# slot_imu.net
KiCad netlist of a schematic drawn in EAGLE
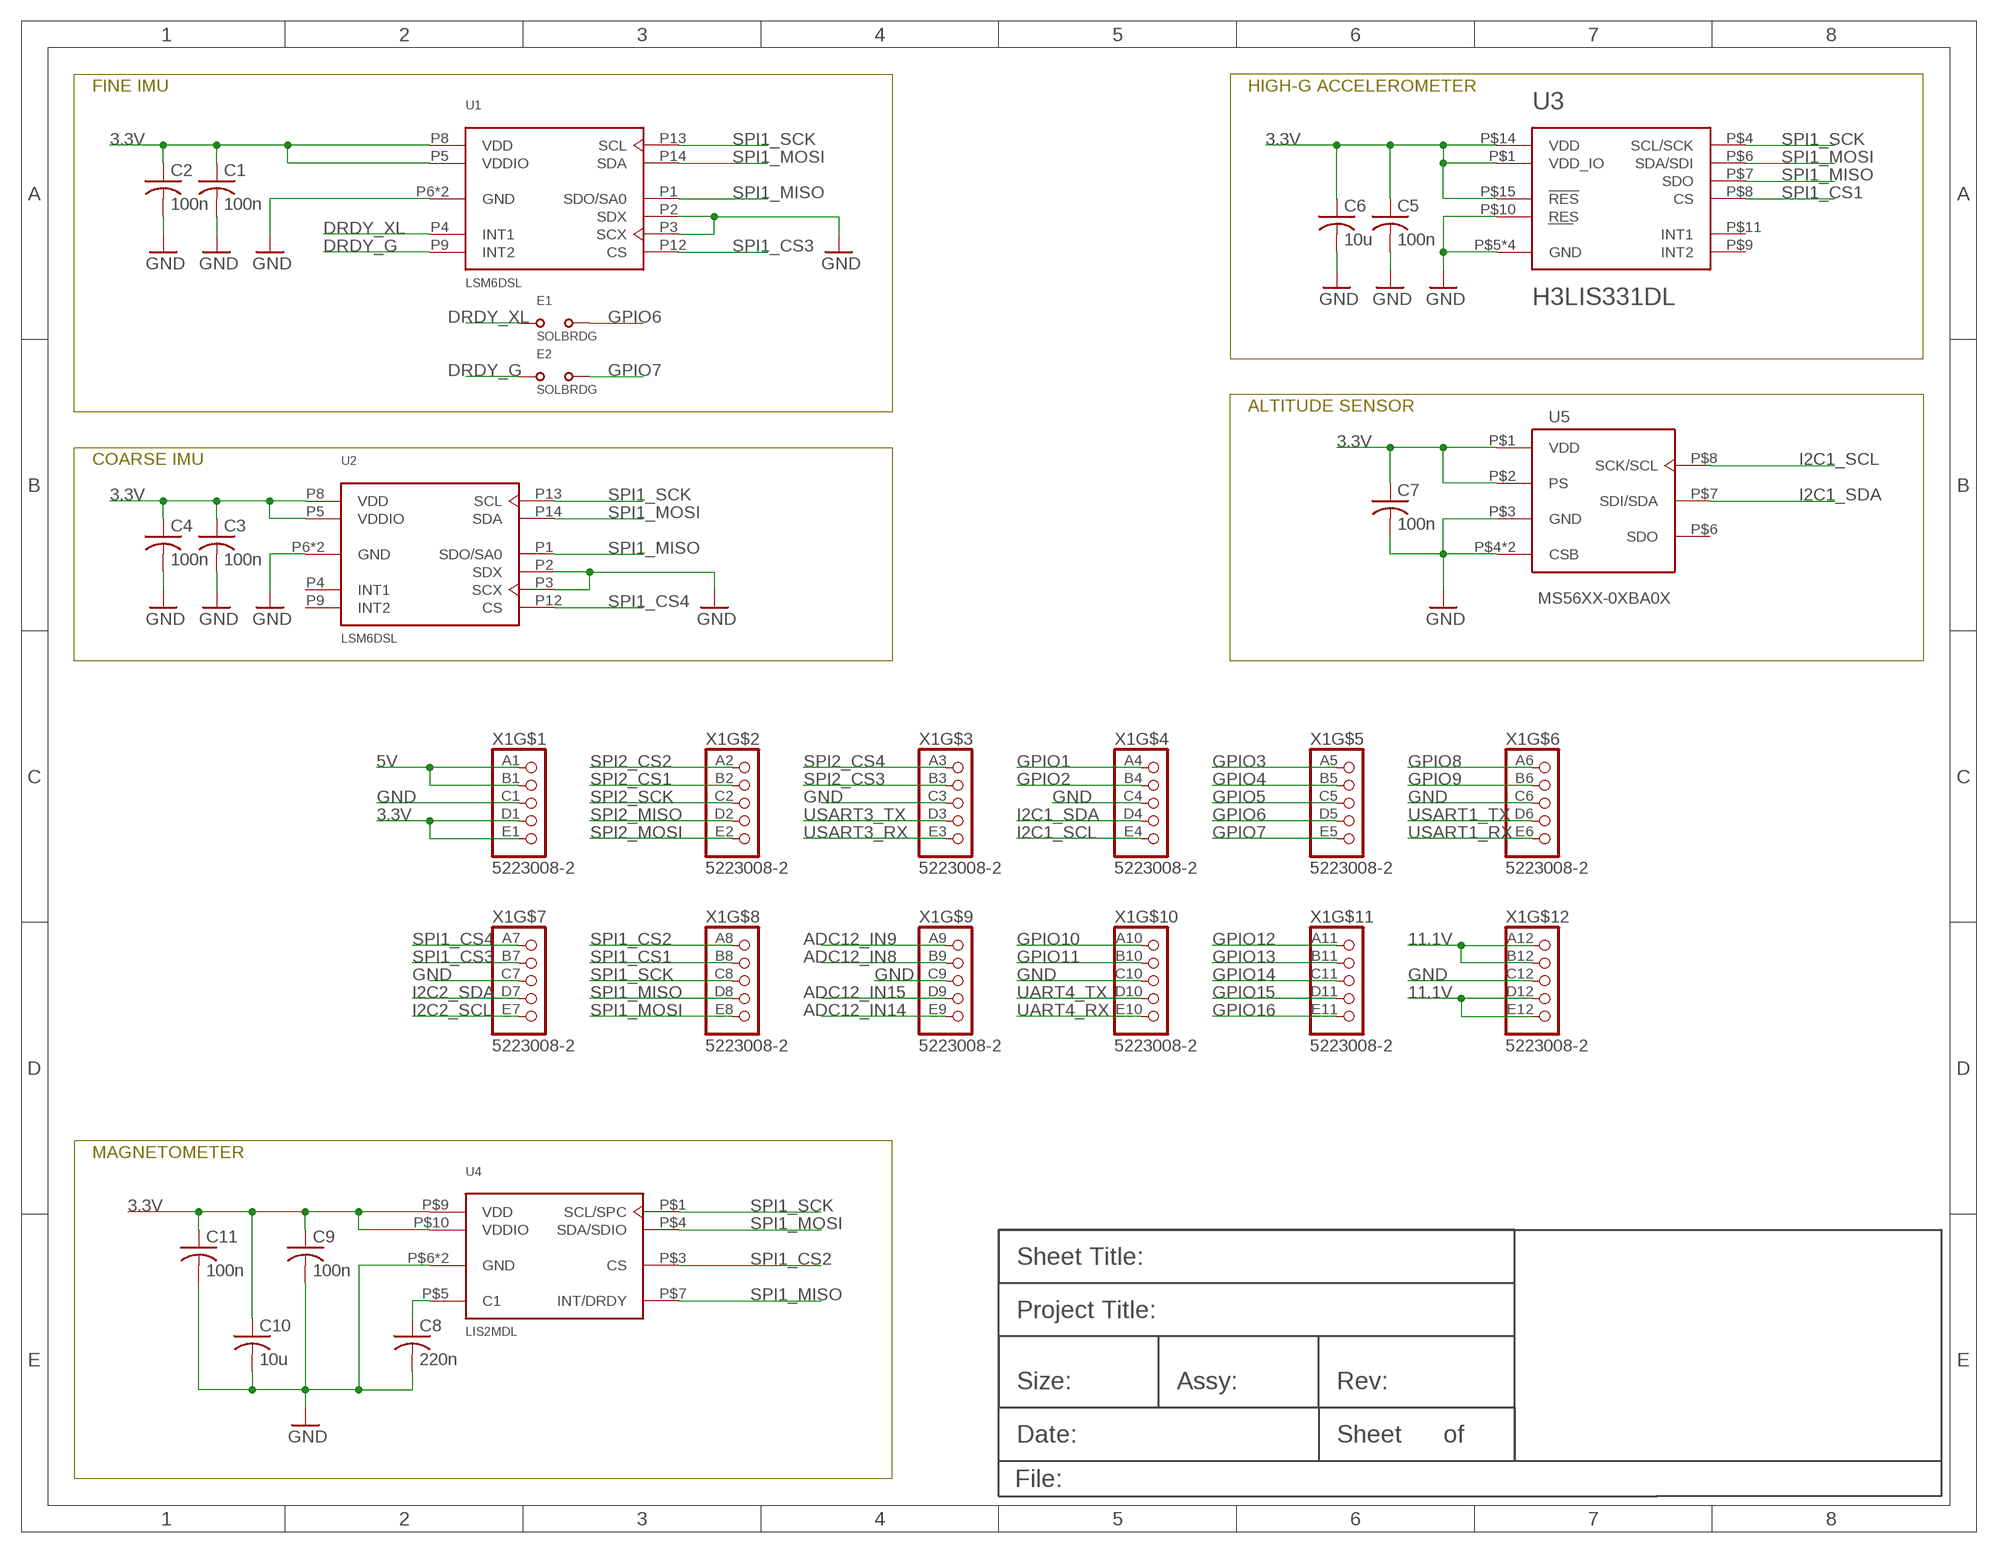
[diagram p0: schematic, sheet 1]

(export (version "E")
  (design (tool "Eeschema 10.0.6"))
  (components
    (comp (ref "C1")
      (value "100n")
      (footprint "eagle-import:C0805")
      (libsource (lib "eagle-import") (part "C-USC0805"))
    )
    (comp (ref "C2")
      (value "100n")
      (footprint "eagle-import:C0805")
      (libsource (lib "eagle-import") (part "C-USC0805"))
    )
    (comp (ref "C3")
      (value "100n")
      (footprint "eagle-import:C0805")
      (libsource (lib "eagle-import") (part "C-USC0805"))
    )
    (comp (ref "C4")
      (value "100n")
      (footprint "eagle-import:C0805")
      (libsource (lib "eagle-import") (part "C-USC0805"))
    )
    (comp (ref "C5")
      (value "100n")
      (footprint "eagle-import:C0805")
      (libsource (lib "eagle-import") (part "C-USC0805"))
    )
    (comp (ref "C6")
      (value "10u")
      (footprint "eagle-import:C0805")
      (libsource (lib "eagle-import") (part "C-USC0805"))
    )
    (comp (ref "C7")
      (value "100n")
      (footprint "eagle-import:C0805")
      (libsource (lib "eagle-import") (part "C-USC0805"))
    )
    (comp (ref "C8")
      (value "220n")
      (footprint "eagle-import:C0805")
      (libsource (lib "eagle-import") (part "C-USC0805"))
    )
    (comp (ref "C9")
      (value "100n")
      (footprint "eagle-import:C0805")
      (libsource (lib "eagle-import") (part "C-USC0805"))
    )
    (comp (ref "C10")
      (value "10u")
      (footprint "eagle-import:C0805")
      (libsource (lib "eagle-import") (part "C-USC0805"))
    )
    (comp (ref "C11")
      (value "100n")
      (footprint "eagle-import:C0805")
      (libsource (lib "eagle-import") (part "C-USC0805"))
    )
    (comp (ref "E1")
      (value "SOLBRDG")
      (footprint "eagle-import:SOLBRDG")
      (libsource (lib "eagle-import") (part "SOLBRDG"))
    )
    (comp (ref "E2")
      (value "SOLBRDG")
      (footprint "eagle-import:SOLBRDG")
      (libsource (lib "eagle-import") (part "SOLBRDG"))
    )
    (comp (ref "U1")
      (value "LSM6DSL")
      (footprint "eagle-import:LGA-14")
      (libsource (lib "eagle-import") (part "LSM6DSL"))
    )
    (comp (ref "U2")
      (value "LSM6DSL")
      (footprint "eagle-import:LGA-14")
      (libsource (lib "eagle-import") (part "LSM6DSL"))
    )
    (comp (ref "U3")
      (value "H3LIS331DL")
      (footprint "eagle-import:TFLGA-16L")
      (libsource (lib "eagle-import") (part "H3LIS331DL"))
    )
    (comp (ref "U4")
      (value "LIS2MDL")
      (footprint "eagle-import:LGA-12")
      (libsource (lib "eagle-import") (part "LIS2MDL"))
    )
    (comp (ref "U5")
      (value "MS56XX-0XBA0X")
      (footprint "eagle-import:MS56XX")
      (libsource (lib "eagle-import") (part "MS56XX-0XBA0X"))
    )
    (comp (ref "X1")
      (value "5223008-2")
      (footprint "eagle-import:5223008-2")
      (libsource (lib "eagle-import") (part "5223008-2"))
    )
  )
  (nets
    (net (code "1") (name "/3.3V") (class "Default")
      (node (ref "C1") (pin "1") (pinfunction "1_1") (pintype "passive"))
      (node (ref "C10") (pin "1") (pinfunction "1_1") (pintype "passive"))
      (node (ref "C11") (pin "1") (pinfunction "1_1") (pintype "passive"))
      (node (ref "C2") (pin "1") (pinfunction "1_1") (pintype "passive"))
      (node (ref "C3") (pin "1") (pinfunction "1_1") (pintype "passive"))
      (node (ref "C4") (pin "1") (pinfunction "1_1") (pintype "passive"))
      (node (ref "C5") (pin "1") (pinfunction "1_1") (pintype "passive"))
      (node (ref "C6") (pin "1") (pinfunction "1_1") (pintype "passive"))
      (node (ref "C7") (pin "1") (pinfunction "1_1") (pintype "passive"))
      (node (ref "C9") (pin "1") (pinfunction "1_1") (pintype "passive"))
      (node (ref "U1") (pin "P5") (pinfunction "VDDIO_P5") (pintype "bidirectional"))
      (node (ref "U1") (pin "P8") (pinfunction "VDD_P8") (pintype "bidirectional"))
      (node (ref "U2") (pin "P5") (pinfunction "VDDIO_P5") (pintype "bidirectional"))
      (node (ref "U2") (pin "P8") (pinfunction "VDD_P8") (pintype "bidirectional"))
      (node (ref "U3") (pin "P$1") (pinfunction "VDD_IO_P$1") (pintype "bidirectional"))
      (node (ref "U3") (pin "P$14") (pinfunction "VDD_P$14") (pintype "bidirectional"))
      (node (ref "U3") (pin "P$15") (pinfunction "~{RES}_P$15") (pintype "bidirectional"))
      (node (ref "U4") (pin "P$10") (pinfunction "VDDIO_P$10") (pintype "bidirectional"))
      (node (ref "U4") (pin "P$9") (pinfunction "VDD_P$9") (pintype "bidirectional"))
      (node (ref "U5") (pin "P$1") (pinfunction "VDD_P$1") (pintype "power_in"))
      (node (ref "U5") (pin "P$2") (pinfunction "PS_P$2") (pintype "input"))
      (node (ref "X1") (pin "D1") (pinfunction "4_D1") (pintype "passive"))
      (node (ref "X1") (pin "E1") (pinfunction "5_E1") (pintype "passive"))
    )
    (net (code "2") (name "/5V") (class "Default")
      (node (ref "X1") (pin "A1") (pinfunction "1_A1") (pintype "passive"))
      (node (ref "X1") (pin "B1") (pinfunction "2_B1") (pintype "passive"))
    )
    (net (code "3") (name "/11.1V") (class "Default")
      (node (ref "X1") (pin "A12") (pinfunction "1_A12") (pintype "passive"))
      (node (ref "X1") (pin "B12") (pinfunction "2_B12") (pintype "passive"))
      (node (ref "X1") (pin "D12") (pinfunction "4_D12") (pintype "passive"))
      (node (ref "X1") (pin "E12") (pinfunction "5_E12") (pintype "passive"))
    )
    (net (code "4") (name "/ADC12_IN8") (class "Default")
      (node (ref "X1") (pin "B9") (pinfunction "2_B9") (pintype "passive"))
    )
    (net (code "5") (name "/ADC12_IN9") (class "Default")
      (node (ref "X1") (pin "A9") (pinfunction "1_A9") (pintype "passive"))
    )
    (net (code "6") (name "/ADC12_IN14") (class "Default")
      (node (ref "X1") (pin "E9") (pinfunction "5_E9") (pintype "passive"))
    )
    (net (code "7") (name "/ADC12_IN15") (class "Default")
      (node (ref "X1") (pin "D9") (pinfunction "4_D9") (pintype "passive"))
    )
    (net (code "8") (name "/DRDY_G") (class "Default")
      (node (ref "E2") (pin "P$1") (pinfunction "P$1_P$1") (pintype "bidirectional"))
      (node (ref "U1") (pin "P9") (pinfunction "INT2_P9") (pintype "bidirectional"))
    )
    (net (code "9") (name "/DRDY_XL") (class "Default")
      (node (ref "E1") (pin "P$1") (pinfunction "P$1_P$1") (pintype "bidirectional"))
      (node (ref "U1") (pin "P4") (pinfunction "INT1_P4") (pintype "bidirectional"))
    )
    (net (code "10") (name "/GPIO1") (class "Default")
      (node (ref "X1") (pin "A4") (pinfunction "1_A4") (pintype "passive"))
    )
    (net (code "11") (name "/GPIO2") (class "Default")
      (node (ref "X1") (pin "B4") (pinfunction "2_B4") (pintype "passive"))
    )
    (net (code "12") (name "/GPIO3") (class "Default")
      (node (ref "X1") (pin "A5") (pinfunction "1_A5") (pintype "passive"))
    )
    (net (code "13") (name "/GPIO4") (class "Default")
      (node (ref "X1") (pin "B5") (pinfunction "2_B5") (pintype "passive"))
    )
    (net (code "14") (name "/GPIO5") (class "Default")
      (node (ref "X1") (pin "C5") (pinfunction "3_C5") (pintype "passive"))
    )
    (net (code "15") (name "/GPIO6") (class "Default")
      (node (ref "E1") (pin "P$2") (pinfunction "P$2_P$2") (pintype "bidirectional"))
      (node (ref "X1") (pin "D5") (pinfunction "4_D5") (pintype "passive"))
    )
    (net (code "16") (name "/GPIO7") (class "Default")
      (node (ref "E2") (pin "P$2") (pinfunction "P$2_P$2") (pintype "bidirectional"))
      (node (ref "X1") (pin "E5") (pinfunction "5_E5") (pintype "passive"))
    )
    (net (code "17") (name "/GPIO8") (class "Default")
      (node (ref "X1") (pin "A6") (pinfunction "1_A6") (pintype "passive"))
    )
    (net (code "18") (name "/GPIO9") (class "Default")
      (node (ref "X1") (pin "B6") (pinfunction "2_B6") (pintype "passive"))
    )
    (net (code "19") (name "/GPIO10") (class "Default")
      (node (ref "X1") (pin "A10") (pinfunction "1_A10") (pintype "passive"))
    )
    (net (code "20") (name "/GPIO11") (class "Default")
      (node (ref "X1") (pin "B10") (pinfunction "2_B10") (pintype "passive"))
    )
    (net (code "21") (name "/GPIO12") (class "Default")
      (node (ref "X1") (pin "A11") (pinfunction "1_A11") (pintype "passive"))
    )
    (net (code "22") (name "/GPIO13") (class "Default")
      (node (ref "X1") (pin "B11") (pinfunction "2_B11") (pintype "passive"))
    )
    (net (code "23") (name "/GPIO14") (class "Default")
      (node (ref "X1") (pin "C11") (pinfunction "3_C11") (pintype "passive"))
    )
    (net (code "24") (name "/GPIO15") (class "Default")
      (node (ref "X1") (pin "D11") (pinfunction "4_D11") (pintype "passive"))
    )
    (net (code "25") (name "/GPIO16") (class "Default")
      (node (ref "X1") (pin "E11") (pinfunction "5_E11") (pintype "passive"))
    )
    (net (code "26") (name "/I2C1_SCL") (class "Default")
      (node (ref "U5") (pin "P$8") (pinfunction "SCK/SCL_P$8") (pintype "input"))
      (node (ref "X1") (pin "E4") (pinfunction "5_E4") (pintype "passive"))
    )
    (net (code "27") (name "/I2C1_SDA") (class "Default")
      (node (ref "U5") (pin "P$7") (pinfunction "SDI/SDA_P$7") (pintype "bidirectional"))
      (node (ref "X1") (pin "D4") (pinfunction "4_D4") (pintype "passive"))
    )
    (net (code "28") (name "/I2C2_SCL") (class "Default")
      (node (ref "X1") (pin "E7") (pinfunction "5_E7") (pintype "passive"))
    )
    (net (code "29") (name "/I2C2_SDA") (class "Default")
      (node (ref "X1") (pin "D7") (pinfunction "4_D7") (pintype "passive"))
    )
    (net (code "30") (name "/SPI1_CS1") (class "Default")
      (node (ref "U3") (pin "P$8") (pinfunction "CS_P$8") (pintype "bidirectional"))
      (node (ref "X1") (pin "B8") (pinfunction "2_B8") (pintype "passive"))
    )
    (net (code "31") (name "/SPI1_CS2") (class "Default")
      (node (ref "U4") (pin "P$3") (pinfunction "CS_P$3") (pintype "bidirectional"))
      (node (ref "X1") (pin "A8") (pinfunction "1_A8") (pintype "passive"))
    )
    (net (code "32") (name "/SPI1_CS3") (class "Default")
      (node (ref "U1") (pin "P12") (pinfunction "CS_P12") (pintype "bidirectional"))
      (node (ref "X1") (pin "B7") (pinfunction "2_B7") (pintype "passive"))
    )
    (net (code "33") (name "/SPI1_CS4") (class "Default")
      (node (ref "U2") (pin "P12") (pinfunction "CS_P12") (pintype "bidirectional"))
      (node (ref "X1") (pin "A7") (pinfunction "1_A7") (pintype "passive"))
    )
    (net (code "34") (name "/SPI1_MISO") (class "Default")
      (node (ref "U1") (pin "P1") (pinfunction "SDO/SA0_P1") (pintype "bidirectional"))
      (node (ref "U2") (pin "P1") (pinfunction "SDO/SA0_P1") (pintype "bidirectional"))
      (node (ref "U3") (pin "P$7") (pinfunction "SDO_P$7") (pintype "bidirectional"))
      (node (ref "U4") (pin "P$7") (pinfunction "INT/DRDY_P$7") (pintype "bidirectional"))
      (node (ref "X1") (pin "D8") (pinfunction "4_D8") (pintype "passive"))
    )
    (net (code "35") (name "/SPI1_MOSI") (class "Default")
      (node (ref "U1") (pin "P14") (pinfunction "SDA_P14") (pintype "bidirectional"))
      (node (ref "U2") (pin "P14") (pinfunction "SDA_P14") (pintype "bidirectional"))
      (node (ref "U3") (pin "P$6") (pinfunction "SDA/SDI_P$6") (pintype "bidirectional"))
      (node (ref "U4") (pin "P$4") (pinfunction "SDA/SDIO_P$4") (pintype "bidirectional"))
      (node (ref "X1") (pin "E8") (pinfunction "5_E8") (pintype "passive"))
    )
    (net (code "36") (name "/SPI1_SCK") (class "Default")
      (node (ref "U1") (pin "P13") (pinfunction "SCL_P13") (pintype "bidirectional"))
      (node (ref "U2") (pin "P13") (pinfunction "SCL_P13") (pintype "bidirectional"))
      (node (ref "U3") (pin "P$4") (pinfunction "SCL/SCK_P$4") (pintype "bidirectional"))
      (node (ref "U4") (pin "P$1") (pinfunction "SCL/SPC_P$1") (pintype "bidirectional"))
      (node (ref "X1") (pin "C8") (pinfunction "3_C8") (pintype "passive"))
    )
    (net (code "37") (name "/SPI2_CS1") (class "Default")
      (node (ref "X1") (pin "B2") (pinfunction "2_B2") (pintype "passive"))
    )
    (net (code "38") (name "/SPI2_CS2") (class "Default")
      (node (ref "X1") (pin "A2") (pinfunction "1_A2") (pintype "passive"))
    )
    (net (code "39") (name "/SPI2_CS3") (class "Default")
      (node (ref "X1") (pin "B3") (pinfunction "2_B3") (pintype "passive"))
    )
    (net (code "40") (name "/SPI2_CS4") (class "Default")
      (node (ref "X1") (pin "A3") (pinfunction "1_A3") (pintype "passive"))
    )
    (net (code "41") (name "/SPI2_MISO") (class "Default")
      (node (ref "X1") (pin "D2") (pinfunction "4_D2") (pintype "passive"))
    )
    (net (code "42") (name "/SPI2_MOSI") (class "Default")
      (node (ref "X1") (pin "E2") (pinfunction "5_E2") (pintype "passive"))
    )
    (net (code "43") (name "/SPI2_SCK") (class "Default")
      (node (ref "X1") (pin "C2") (pinfunction "3_C2") (pintype "passive"))
    )
    (net (code "44") (name "/UART4_RX") (class "Default")
      (node (ref "X1") (pin "E10") (pinfunction "5_E10") (pintype "passive"))
    )
    (net (code "45") (name "/UART4_TX") (class "Default")
      (node (ref "X1") (pin "D10") (pinfunction "4_D10") (pintype "passive"))
    )
    (net (code "46") (name "/USART1_RX") (class "Default")
      (node (ref "X1") (pin "E6") (pinfunction "5_E6") (pintype "passive"))
    )
    (net (code "47") (name "/USART1_TX") (class "Default")
      (node (ref "X1") (pin "D6") (pinfunction "4_D6") (pintype "passive"))
    )
    (net (code "48") (name "/USART3_RX") (class "Default")
      (node (ref "X1") (pin "E3") (pinfunction "5_E3") (pintype "passive"))
    )
    (net (code "49") (name "/USART3_TX") (class "Default")
      (node (ref "X1") (pin "D3") (pinfunction "4_D3") (pintype "passive"))
    )
    (net (code "50") (name "GND") (class "Default")
      (node (ref "C1") (pin "2") (pinfunction "2_2") (pintype "passive"))
      (node (ref "C10") (pin "2") (pinfunction "2_2") (pintype "passive"))
      (node (ref "C11") (pin "2") (pinfunction "2_2") (pintype "passive"))
      (node (ref "C2") (pin "2") (pinfunction "2_2") (pintype "passive"))
      (node (ref "C3") (pin "2") (pinfunction "2_2") (pintype "passive"))
      (node (ref "C4") (pin "2") (pinfunction "2_2") (pintype "passive"))
      (node (ref "C5") (pin "2") (pinfunction "2_2") (pintype "passive"))
      (node (ref "C6") (pin "2") (pinfunction "2_2") (pintype "passive"))
      (node (ref "C7") (pin "2") (pinfunction "2_2") (pintype "passive"))
      (node (ref "C8") (pin "2") (pinfunction "2_2") (pintype "passive"))
      (node (ref "C9") (pin "2") (pinfunction "2_2") (pintype "passive"))
      (node (ref "U1") (pin "P2") (pinfunction "SDX_P2") (pintype "bidirectional"))
      (node (ref "U1") (pin "P3") (pinfunction "SCX_P3") (pintype "bidirectional"))
      (node (ref "U1") (pin "P6") (pinfunction "GND_P6") (pintype "bidirectional"))
      (node (ref "U1") (pin "P7") (pinfunction "GND_P7") (pintype "bidirectional"))
      (node (ref "U2") (pin "P2") (pinfunction "SDX_P2") (pintype "bidirectional"))
      (node (ref "U2") (pin "P3") (pinfunction "SCX_P3") (pintype "bidirectional"))
      (node (ref "U2") (pin "P6") (pinfunction "GND_P6") (pintype "bidirectional"))
      (node (ref "U2") (pin "P7") (pinfunction "GND_P7") (pintype "bidirectional"))
      (node (ref "U3") (pin "P$10") (pinfunction "RES_P$10") (pintype "bidirectional"))
      (node (ref "U3") (pin "P$12") (pinfunction "GND_P$12") (pintype "bidirectional"))
      (node (ref "U3") (pin "P$13") (pinfunction "GND_P$13") (pintype "bidirectional"))
      (node (ref "U3") (pin "P$16") (pinfunction "GND_P$16") (pintype "bidirectional"))
      (node (ref "U3") (pin "P$5") (pinfunction "GND_P$5") (pintype "bidirectional"))
      (node (ref "U4") (pin "P$6") (pinfunction "GND_P$6") (pintype "bidirectional"))
      (node (ref "U4") (pin "P$8") (pinfunction "GND_P$8") (pintype "bidirectional"))
      (node (ref "U5") (pin "P$3") (pinfunction "GND_P$3") (pintype "power_in"))
      (node (ref "U5") (pin "P$4") (pinfunction "CSB_P$4") (pintype "input"))
      (node (ref "U5") (pin "P$5") (pinfunction "CSB_P$5") (pintype "input"))
      (node (ref "X1") (pin "C1") (pinfunction "3_C1") (pintype "passive"))
      (node (ref "X1") (pin "C10") (pinfunction "3_C10") (pintype "passive"))
      (node (ref "X1") (pin "C12") (pinfunction "3_C12") (pintype "passive"))
      (node (ref "X1") (pin "C3") (pinfunction "3_C3") (pintype "passive"))
      (node (ref "X1") (pin "C4") (pinfunction "3_C4") (pintype "passive"))
      (node (ref "X1") (pin "C6") (pinfunction "3_C6") (pintype "passive"))
      (node (ref "X1") (pin "C7") (pinfunction "3_C7") (pintype "passive"))
      (node (ref "X1") (pin "C9") (pinfunction "3_C9") (pintype "passive"))
    )
    (net (code "51") (name "Net-(U4-C1)") (class "Default")
      (node (ref "C8") (pin "1") (pinfunction "1_1") (pintype "passive"))
      (node (ref "U4") (pin "P$5") (pinfunction "C1_P$5") (pintype "bidirectional"))
    )
    (net (code "52") (name "unconnected-(U2-INT1-PadP4)") (class "Default")
      (node (ref "U2") (pin "P4") (pinfunction "INT1_P4") (pintype "bidirectional"))
    )
    (net (code "53") (name "unconnected-(U2-INT2-PadP9)") (class "Default")
      (node (ref "U2") (pin "P9") (pinfunction "INT2_P9") (pintype "bidirectional"))
    )
    (net (code "54") (name "unconnected-(U3-INT1-PadP$11)") (class "Default")
      (node (ref "U3") (pin "P$11") (pinfunction "INT1_P$11") (pintype "bidirectional"))
    )
    (net (code "55") (name "unconnected-(U3-INT2-PadP$9)") (class "Default")
      (node (ref "U3") (pin "P$9") (pinfunction "INT2_P$9") (pintype "bidirectional"))
    )
    (net (code "56") (name "unconnected-(U5-SDO-PadP$6)") (class "Default")
      (node (ref "U5") (pin "P$6") (pinfunction "SDO_P$6") (pintype "output"))
    )
  )
)
